# design.net
KiCad netlist of a schematic drawn in EasyEDA Pro
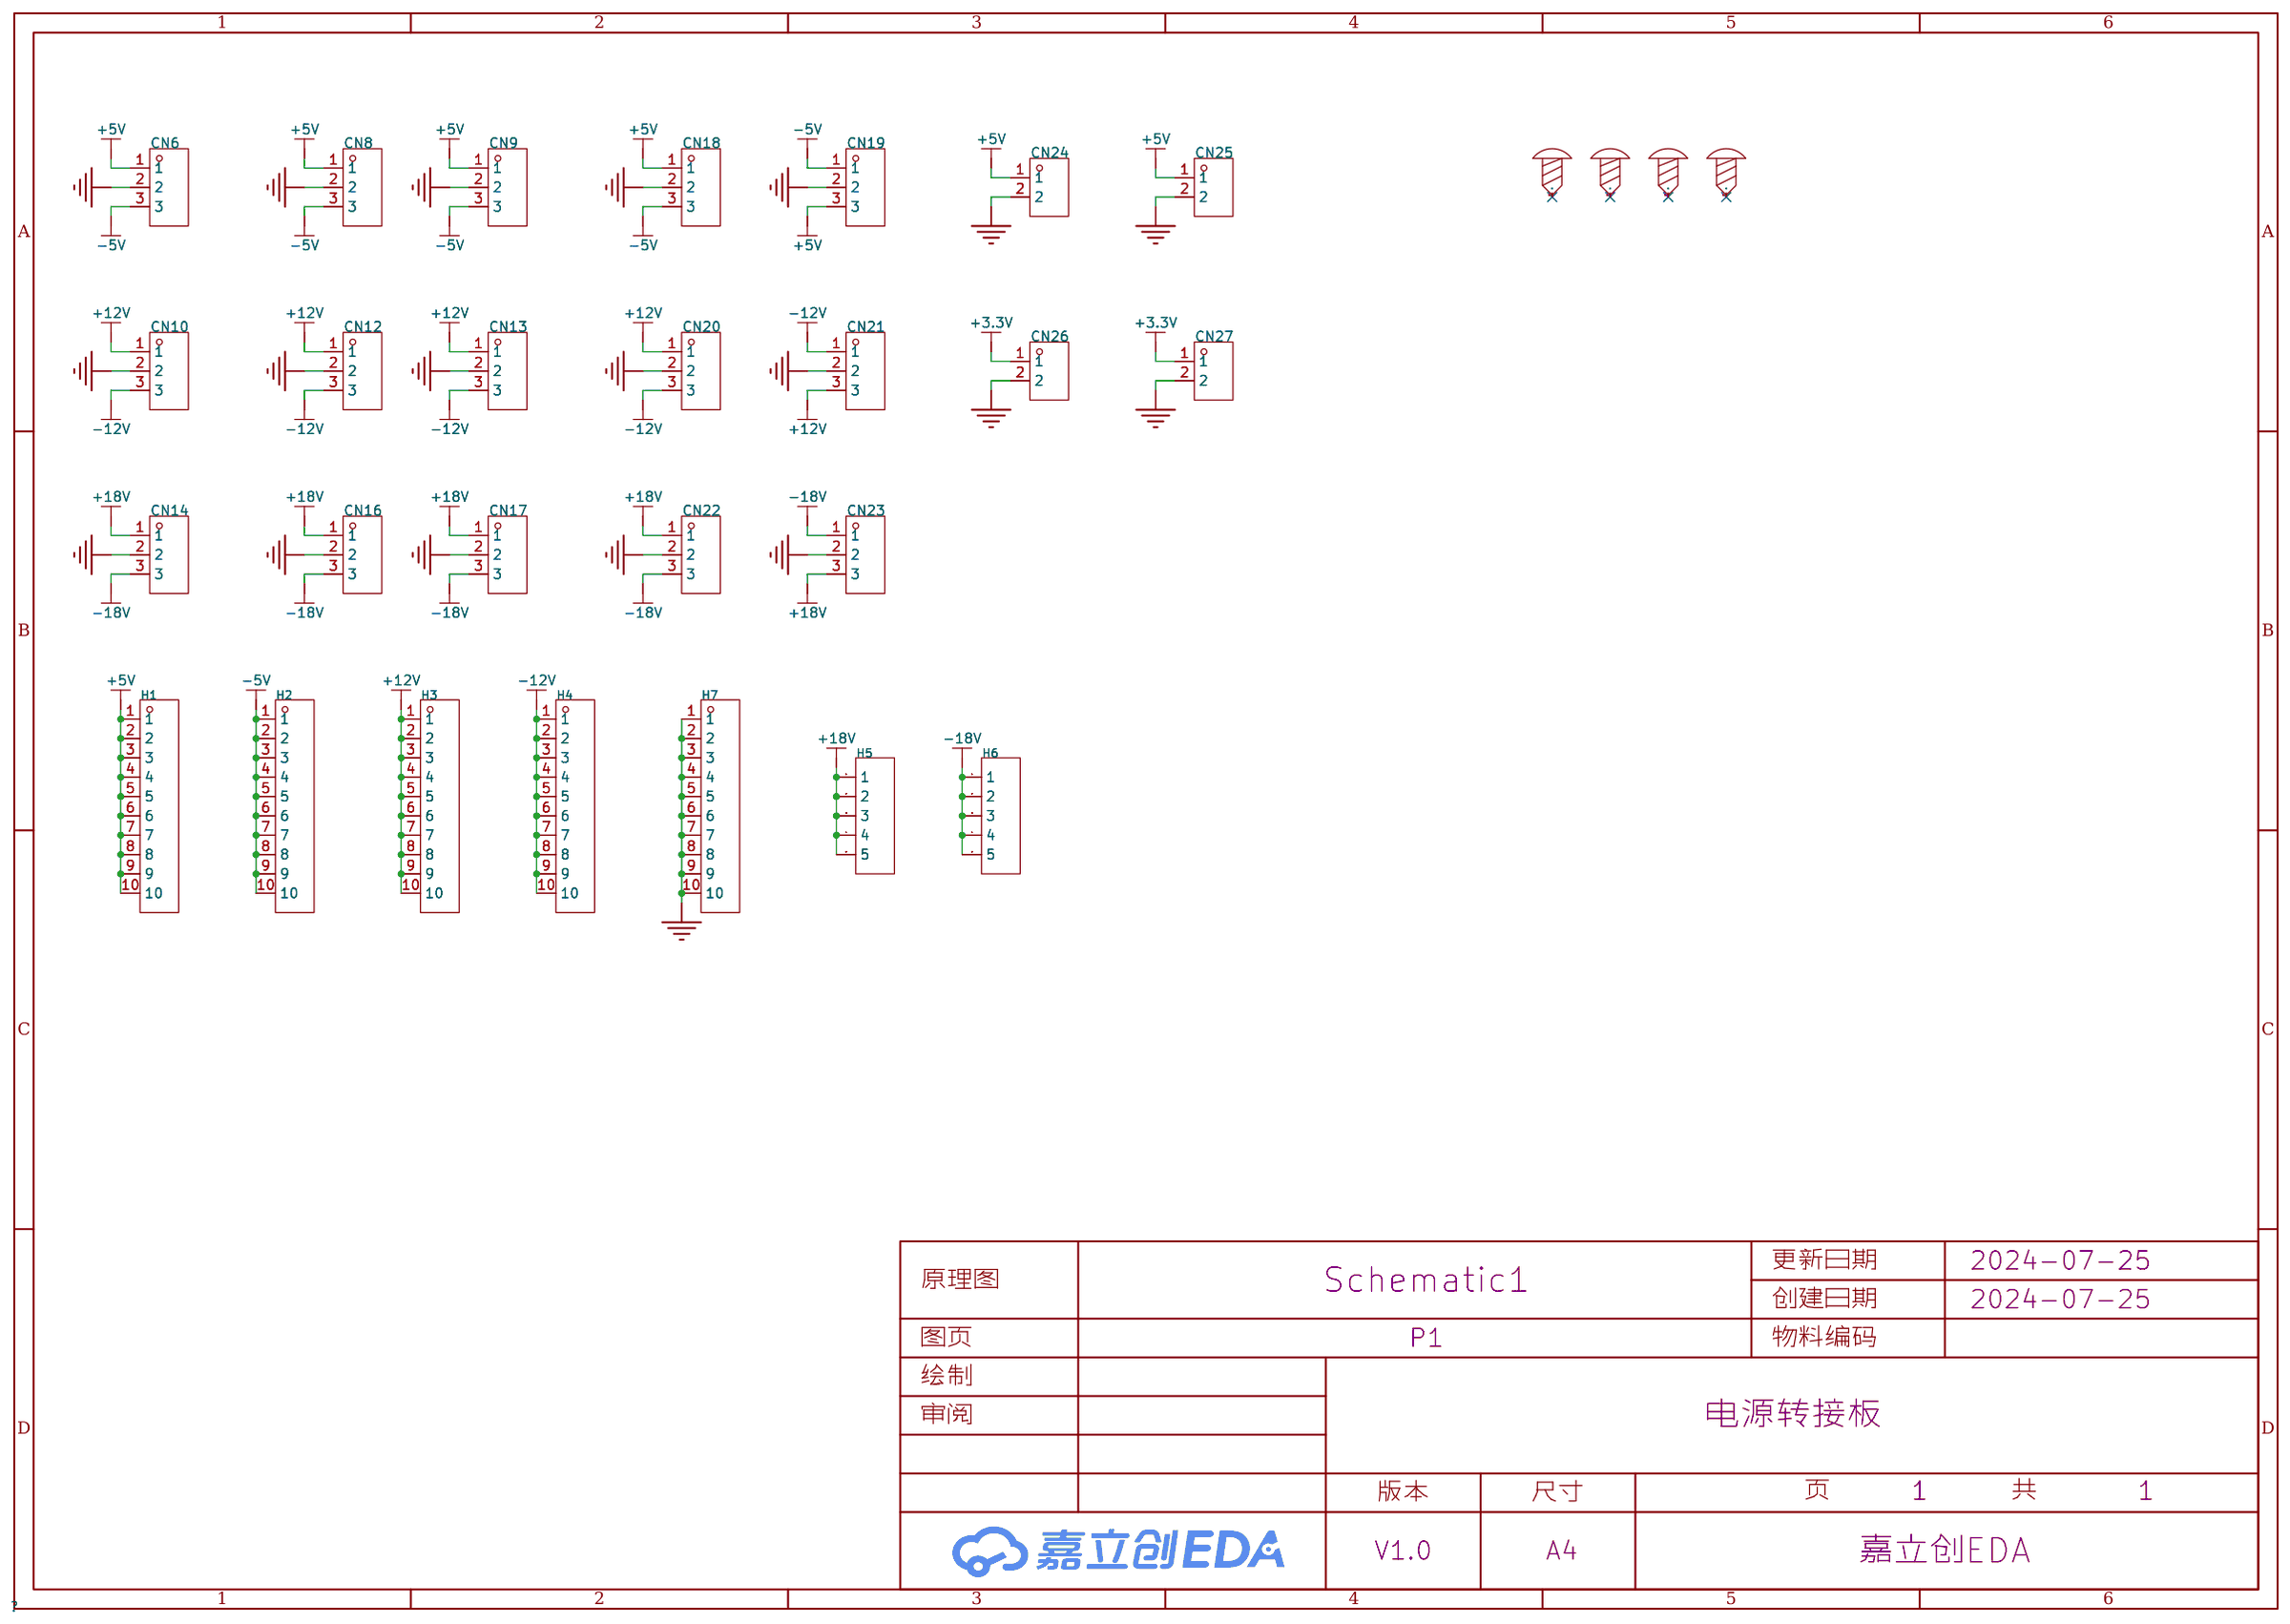
[diagram p0: schematic sheet]

(export (version "E")
  (design (tool "Eeschema 10.0.6"))
  (components
    (comp (ref "CN6")
      (value "DB2EVC-3.81-3P-GN")
      (footprint "easyedapro:CONN-TH_3P-P3.81_DB2EVC-3.81-3P")
      (fields (field (name "Manufacturer") "DORABO(地博电气)"))
      (libsource (lib "easyedapro") (part "DB2EVC-3.81-3P"))
    )
    (comp (ref "CN8")
      (value "DB2EVC-3.81-3P-GN")
      (footprint "easyedapro:CONN-TH_3P-P3.81_DB2EVC-3.81-3P")
      (fields (field (name "Manufacturer") "DORABO(地博电气)"))
      (libsource (lib "easyedapro") (part "DB2EVC-3.81-3P"))
    )
    (comp (ref "CN9")
      (value "DB2EVC-3.81-3P-GN")
      (footprint "easyedapro:CONN-TH_3P-P3.81_DB2EVC-3.81-3P")
      (fields (field (name "Manufacturer") "DORABO(地博电气)"))
      (libsource (lib "easyedapro") (part "DB2EVC-3.81-3P"))
    )
    (comp (ref "CN10")
      (value "DB2EVC-3.81-3P-GN")
      (footprint "easyedapro:CONN-TH_3P-P3.81_DB2EVC-3.81-3P")
      (fields (field (name "Manufacturer") "DORABO(地博电气)"))
      (libsource (lib "easyedapro") (part "DB2EVC-3.81-3P"))
    )
    (comp (ref "CN12")
      (value "DB2EVC-3.81-3P-GN")
      (footprint "easyedapro:CONN-TH_3P-P3.81_DB2EVC-3.81-3P")
      (fields (field (name "Manufacturer") "DORABO(地博电气)"))
      (libsource (lib "easyedapro") (part "DB2EVC-3.81-3P"))
    )
    (comp (ref "CN13")
      (value "DB2EVC-3.81-3P-GN")
      (footprint "easyedapro:CONN-TH_3P-P3.81_DB2EVC-3.81-3P")
      (fields (field (name "Manufacturer") "DORABO(地博电气)"))
      (libsource (lib "easyedapro") (part "DB2EVC-3.81-3P"))
    )
    (comp (ref "CN14")
      (value "DB2EVC-3.81-3P-GN")
      (footprint "easyedapro:CONN-TH_3P-P3.81_DB2EVC-3.81-3P")
      (fields (field (name "Manufacturer") "DORABO(地博电气)"))
      (libsource (lib "easyedapro") (part "DB2EVC-3.81-3P"))
    )
    (comp (ref "CN16")
      (value "DB2EVC-3.81-3P-GN")
      (footprint "easyedapro:CONN-TH_3P-P3.81_DB2EVC-3.81-3P")
      (fields (field (name "Manufacturer") "DORABO(地博电气)"))
      (libsource (lib "easyedapro") (part "DB2EVC-3.81-3P"))
    )
    (comp (ref "CN17")
      (value "DB2EVC-3.81-3P-GN")
      (footprint "easyedapro:CONN-TH_3P-P3.81_DB2EVC-3.81-3P")
      (fields (field (name "Manufacturer") "DORABO(地博电气)"))
      (libsource (lib "easyedapro") (part "DB2EVC-3.81-3P"))
    )
    (comp (ref "CN18")
      (value "MX301-5.0-03P-BU01-Cu-Y-A")
      (footprint "easyedapro:CONN-TH_3P-P5.0-MX301-5.0-03P-BU01-CU-Y-A")
      (fields (field (name "Manufacturer") "MAX(迈旭)"))
      (libsource (lib "easyedapro") (part "MX301-5.0-03P-BU01-CU-Y-A"))
    )
    (comp (ref "CN19")
      (value "MX301-5.0-03P-BU01-Cu-Y-A")
      (footprint "easyedapro:CONN-TH_3P-P5.0-MX301-5.0-03P-BU01-CU-Y-A")
      (fields (field (name "Manufacturer") "MAX(迈旭)"))
      (libsource (lib "easyedapro") (part "MX301-5.0-03P-BU01-CU-Y-A"))
    )
    (comp (ref "CN20")
      (value "MX301-5.0-03P-BU01-Cu-Y-A")
      (footprint "easyedapro:CONN-TH_3P-P5.0-MX301-5.0-03P-BU01-CU-Y-A")
      (fields (field (name "Manufacturer") "MAX(迈旭)"))
      (libsource (lib "easyedapro") (part "MX301-5.0-03P-BU01-CU-Y-A"))
    )
    (comp (ref "CN21")
      (value "MX301-5.0-03P-BU01-Cu-Y-A")
      (footprint "easyedapro:CONN-TH_3P-P5.0-MX301-5.0-03P-BU01-CU-Y-A")
      (fields (field (name "Manufacturer") "MAX(迈旭)"))
      (libsource (lib "easyedapro") (part "MX301-5.0-03P-BU01-CU-Y-A"))
    )
    (comp (ref "CN22")
      (value "MX301-5.0-03P-BU01-Cu-Y-A")
      (footprint "easyedapro:CONN-TH_3P-P5.0-MX301-5.0-03P-BU01-CU-Y-A")
      (fields (field (name "Manufacturer") "MAX(迈旭)"))
      (libsource (lib "easyedapro") (part "MX301-5.0-03P-BU01-CU-Y-A"))
    )
    (comp (ref "CN23")
      (value "MX301-5.0-03P-BU01-Cu-Y-A")
      (footprint "easyedapro:CONN-TH_3P-P5.0-MX301-5.0-03P-BU01-CU-Y-A")
      (fields (field (name "Manufacturer") "MAX(迈旭)"))
      (libsource (lib "easyedapro") (part "MX301-5.0-03P-BU01-CU-Y-A"))
    )
    (comp (ref "CN24")
      (value "ZX-XH2.54-2PZZ")
      (footprint "easyedapro:CONN-TH_2P-P2.50_HX25003-2A")
      (fields (field (name "Manufacturer") "Megastar(兆星)"))
      (libsource (lib "easyedapro") (part "ZX-XH2.54-2PZZ"))
    )
    (comp (ref "CN25")
      (value "ZX-XH2.54-2PZZ")
      (footprint "easyedapro:CONN-TH_2P-P2.50_HX25003-2A")
      (fields (field (name "Manufacturer") "Megastar(兆星)"))
      (libsource (lib "easyedapro") (part "ZX-XH2.54-2PZZ"))
    )
    (comp (ref "CN26")
      (value "ZX-XH2.54-2PZZ")
      (footprint "easyedapro:CONN-TH_2P-P2.50_HX25003-2A")
      (fields (field (name "Manufacturer") "Megastar(兆星)"))
      (libsource (lib "easyedapro") (part "ZX-XH2.54-2PZZ"))
    )
    (comp (ref "CN27")
      (value "ZX-XH2.54-2PZZ")
      (footprint "easyedapro:CONN-TH_2P-P2.50_HX25003-2A")
      (fields (field (name "Manufacturer") "Megastar(兆星)"))
      (libsource (lib "easyedapro") (part "ZX-XH2.54-2PZZ"))
    )
    (comp (ref "H1")
      (value "~")
      (footprint "easyedapro:HDR-TH_10P-P2.54-V-F")
      (libsource (lib "easyedapro") (part "X5511FV-10-C70D30-1000"))
    )
    (comp (ref "H2")
      (value "~")
      (footprint "easyedapro:HDR-TH_10P-P2.54-V-F")
      (libsource (lib "easyedapro") (part "X5511FV-10-C70D30-1000"))
    )
    (comp (ref "H3")
      (value "~")
      (footprint "easyedapro:HDR-TH_10P-P2.54-V-F")
      (libsource (lib "easyedapro") (part "X5511FV-10-C70D30-1000"))
    )
    (comp (ref "H4")
      (value "~")
      (footprint "easyedapro:HDR-TH_10P-P2.54-V-F")
      (libsource (lib "easyedapro") (part "X5511FV-10-C70D30-1000"))
    )
    (comp (ref "H5")
      (value "~")
      (footprint "easyedapro:HDR-TH_5P-P2.54-V-F")
      (libsource (lib "easyedapro") (part "Header-Female-2.54_1x5"))
    )
    (comp (ref "H6")
      (value "~")
      (footprint "easyedapro:HDR-TH_5P-P2.54-V-F")
      (libsource (lib "easyedapro") (part "Header-Female-2.54_1x5"))
    )
    (comp (ref "H7")
      (value "~")
      (footprint "easyedapro:HDR-TH_10P-P2.54-V-F")
      (libsource (lib "easyedapro") (part "X5511FV-10-C70D30-1000"))
    )
    (comp (ref "TP1") (value "~") (footprint "easyedapro:M3螺丝") (libsource (lib "easyedapro") (part "螺丝孔")))
    (comp (ref "TP2") (value "~") (footprint "easyedapro:M3螺丝") (libsource (lib "easyedapro") (part "螺丝孔")))
    (comp (ref "TP3") (value "~") (footprint "easyedapro:M3螺丝") (libsource (lib "easyedapro") (part "螺丝孔")))
    (comp (ref "TP4") (value "~") (footprint "easyedapro:M3螺丝") (libsource (lib "easyedapro") (part "螺丝孔")))
  )
  (nets
    (net (code "1") (name "+3.3V") (class "Default")
      (node (ref "CN26") (pin "1") (pinfunction "1_1") (pintype "unspecified"))
      (node (ref "CN27") (pin "1") (pinfunction "1_1") (pintype "unspecified"))
    )
    (net (code "2") (name "+5V") (class "Default")
      (node (ref "CN18") (pin "1") (pinfunction "1_1") (pintype "unspecified"))
      (node (ref "CN19") (pin "3") (pinfunction "3_3") (pintype "unspecified"))
      (node (ref "CN24") (pin "1") (pinfunction "1_1") (pintype "unspecified"))
      (node (ref "CN25") (pin "1") (pinfunction "1_1") (pintype "unspecified"))
      (node (ref "CN6") (pin "1") (pinfunction "1_1") (pintype "unspecified"))
      (node (ref "CN8") (pin "1") (pinfunction "1_1") (pintype "unspecified"))
      (node (ref "CN9") (pin "1") (pinfunction "1_1") (pintype "unspecified"))
      (node (ref "H1") (pin "1") (pinfunction "1_1") (pintype "input"))
      (node (ref "H1") (pin "10") (pinfunction "10_10") (pintype "input"))
      (node (ref "H1") (pin "2") (pinfunction "2_2") (pintype "input"))
      (node (ref "H1") (pin "3") (pinfunction "3_3") (pintype "input"))
      (node (ref "H1") (pin "4") (pinfunction "4_4") (pintype "input"))
      (node (ref "H1") (pin "5") (pinfunction "5_5") (pintype "input"))
      (node (ref "H1") (pin "6") (pinfunction "6_6") (pintype "input"))
      (node (ref "H1") (pin "7") (pinfunction "7_7") (pintype "input"))
      (node (ref "H1") (pin "8") (pinfunction "8_8") (pintype "input"))
      (node (ref "H1") (pin "9") (pinfunction "9_9") (pintype "input"))
    )
    (net (code "3") (name "+12V") (class "Default")
      (node (ref "CN10") (pin "1") (pinfunction "1_1") (pintype "unspecified"))
      (node (ref "CN12") (pin "1") (pinfunction "1_1") (pintype "unspecified"))
      (node (ref "CN13") (pin "1") (pinfunction "1_1") (pintype "unspecified"))
      (node (ref "CN20") (pin "1") (pinfunction "1_1") (pintype "unspecified"))
      (node (ref "CN21") (pin "3") (pinfunction "3_3") (pintype "unspecified"))
      (node (ref "H3") (pin "1") (pinfunction "1_1") (pintype "input"))
      (node (ref "H3") (pin "10") (pinfunction "10_10") (pintype "input"))
      (node (ref "H3") (pin "2") (pinfunction "2_2") (pintype "input"))
      (node (ref "H3") (pin "3") (pinfunction "3_3") (pintype "input"))
      (node (ref "H3") (pin "4") (pinfunction "4_4") (pintype "input"))
      (node (ref "H3") (pin "5") (pinfunction "5_5") (pintype "input"))
      (node (ref "H3") (pin "6") (pinfunction "6_6") (pintype "input"))
      (node (ref "H3") (pin "7") (pinfunction "7_7") (pintype "input"))
      (node (ref "H3") (pin "8") (pinfunction "8_8") (pintype "input"))
      (node (ref "H3") (pin "9") (pinfunction "9_9") (pintype "input"))
    )
    (net (code "4") (name "+18V") (class "Default")
      (node (ref "CN14") (pin "1") (pinfunction "1_1") (pintype "unspecified"))
      (node (ref "CN16") (pin "1") (pinfunction "1_1") (pintype "unspecified"))
      (node (ref "CN17") (pin "1") (pinfunction "1_1") (pintype "unspecified"))
      (node (ref "CN22") (pin "1") (pinfunction "1_1") (pintype "unspecified"))
      (node (ref "CN23") (pin "3") (pinfunction "3_3") (pintype "unspecified"))
      (node (ref "H5") (pin "1") (pinfunction "1_1") (pintype "input"))
      (node (ref "H5") (pin "2") (pinfunction "2_2") (pintype "input"))
      (node (ref "H5") (pin "3") (pinfunction "3_3") (pintype "input"))
      (node (ref "H5") (pin "4") (pinfunction "4_4") (pintype "input"))
      (node (ref "H5") (pin "5") (pinfunction "5_5") (pintype "input"))
    )
    (net (code "5") (name "-5V") (class "Default")
      (node (ref "CN18") (pin "3") (pinfunction "3_3") (pintype "unspecified"))
      (node (ref "CN19") (pin "1") (pinfunction "1_1") (pintype "unspecified"))
      (node (ref "CN6") (pin "3") (pinfunction "3_3") (pintype "unspecified"))
      (node (ref "CN8") (pin "3") (pinfunction "3_3") (pintype "unspecified"))
      (node (ref "CN9") (pin "3") (pinfunction "3_3") (pintype "unspecified"))
      (node (ref "H2") (pin "1") (pinfunction "1_1") (pintype "input"))
      (node (ref "H2") (pin "10") (pinfunction "10_10") (pintype "input"))
      (node (ref "H2") (pin "2") (pinfunction "2_2") (pintype "input"))
      (node (ref "H2") (pin "3") (pinfunction "3_3") (pintype "input"))
      (node (ref "H2") (pin "4") (pinfunction "4_4") (pintype "input"))
      (node (ref "H2") (pin "5") (pinfunction "5_5") (pintype "input"))
      (node (ref "H2") (pin "6") (pinfunction "6_6") (pintype "input"))
      (node (ref "H2") (pin "7") (pinfunction "7_7") (pintype "input"))
      (node (ref "H2") (pin "8") (pinfunction "8_8") (pintype "input"))
      (node (ref "H2") (pin "9") (pinfunction "9_9") (pintype "input"))
    )
    (net (code "6") (name "-12V") (class "Default")
      (node (ref "CN10") (pin "3") (pinfunction "3_3") (pintype "unspecified"))
      (node (ref "CN12") (pin "3") (pinfunction "3_3") (pintype "unspecified"))
      (node (ref "CN13") (pin "3") (pinfunction "3_3") (pintype "unspecified"))
      (node (ref "CN20") (pin "3") (pinfunction "3_3") (pintype "unspecified"))
      (node (ref "CN21") (pin "1") (pinfunction "1_1") (pintype "unspecified"))
      (node (ref "H4") (pin "1") (pinfunction "1_1") (pintype "input"))
      (node (ref "H4") (pin "10") (pinfunction "10_10") (pintype "input"))
      (node (ref "H4") (pin "2") (pinfunction "2_2") (pintype "input"))
      (node (ref "H4") (pin "3") (pinfunction "3_3") (pintype "input"))
      (node (ref "H4") (pin "4") (pinfunction "4_4") (pintype "input"))
      (node (ref "H4") (pin "5") (pinfunction "5_5") (pintype "input"))
      (node (ref "H4") (pin "6") (pinfunction "6_6") (pintype "input"))
      (node (ref "H4") (pin "7") (pinfunction "7_7") (pintype "input"))
      (node (ref "H4") (pin "8") (pinfunction "8_8") (pintype "input"))
      (node (ref "H4") (pin "9") (pinfunction "9_9") (pintype "input"))
    )
    (net (code "7") (name "-18V") (class "Default")
      (node (ref "CN14") (pin "3") (pinfunction "3_3") (pintype "unspecified"))
      (node (ref "CN16") (pin "3") (pinfunction "3_3") (pintype "unspecified"))
      (node (ref "CN17") (pin "3") (pinfunction "3_3") (pintype "unspecified"))
      (node (ref "CN22") (pin "3") (pinfunction "3_3") (pintype "unspecified"))
      (node (ref "CN23") (pin "1") (pinfunction "1_1") (pintype "unspecified"))
      (node (ref "H6") (pin "1") (pinfunction "1_1") (pintype "input"))
      (node (ref "H6") (pin "2") (pinfunction "2_2") (pintype "input"))
      (node (ref "H6") (pin "3") (pinfunction "3_3") (pintype "input"))
      (node (ref "H6") (pin "4") (pinfunction "4_4") (pintype "input"))
      (node (ref "H6") (pin "5") (pinfunction "5_5") (pintype "input"))
    )
    (net (code "8") (name "GND") (class "Default")
      (node (ref "CN10") (pin "2") (pinfunction "2_2") (pintype "unspecified"))
      (node (ref "CN12") (pin "2") (pinfunction "2_2") (pintype "unspecified"))
      (node (ref "CN13") (pin "2") (pinfunction "2_2") (pintype "unspecified"))
      (node (ref "CN14") (pin "2") (pinfunction "2_2") (pintype "unspecified"))
      (node (ref "CN16") (pin "2") (pinfunction "2_2") (pintype "unspecified"))
      (node (ref "CN17") (pin "2") (pinfunction "2_2") (pintype "unspecified"))
      (node (ref "CN18") (pin "2") (pinfunction "2_2") (pintype "unspecified"))
      (node (ref "CN19") (pin "2") (pinfunction "2_2") (pintype "unspecified"))
      (node (ref "CN20") (pin "2") (pinfunction "2_2") (pintype "unspecified"))
      (node (ref "CN21") (pin "2") (pinfunction "2_2") (pintype "unspecified"))
      (node (ref "CN22") (pin "2") (pinfunction "2_2") (pintype "unspecified"))
      (node (ref "CN23") (pin "2") (pinfunction "2_2") (pintype "unspecified"))
      (node (ref "CN24") (pin "2") (pinfunction "2_2") (pintype "unspecified"))
      (node (ref "CN25") (pin "2") (pinfunction "2_2") (pintype "unspecified"))
      (node (ref "CN26") (pin "2") (pinfunction "2_2") (pintype "unspecified"))
      (node (ref "CN27") (pin "2") (pinfunction "2_2") (pintype "unspecified"))
      (node (ref "CN6") (pin "2") (pinfunction "2_2") (pintype "unspecified"))
      (node (ref "CN8") (pin "2") (pinfunction "2_2") (pintype "unspecified"))
      (node (ref "CN9") (pin "2") (pinfunction "2_2") (pintype "unspecified"))
      (node (ref "H7") (pin "1") (pinfunction "1_1") (pintype "input"))
      (node (ref "H7") (pin "10") (pinfunction "10_10") (pintype "input"))
      (node (ref "H7") (pin "2") (pinfunction "2_2") (pintype "input"))
      (node (ref "H7") (pin "3") (pinfunction "3_3") (pintype "input"))
      (node (ref "H7") (pin "4") (pinfunction "4_4") (pintype "input"))
      (node (ref "H7") (pin "5") (pinfunction "5_5") (pintype "input"))
      (node (ref "H7") (pin "6") (pinfunction "6_6") (pintype "input"))
      (node (ref "H7") (pin "7") (pinfunction "7_7") (pintype "input"))
      (node (ref "H7") (pin "8") (pinfunction "8_8") (pintype "input"))
      (node (ref "H7") (pin "9") (pinfunction "9_9") (pintype "input"))
    )
    (net (code "9") (name "unconnected-(TP1-Pad1)") (class "Default")
      (node (ref "TP1") (pin "1") (pinfunction "1_1") (pintype "input+no_connect"))
    )
    (net (code "10") (name "unconnected-(TP2-Pad1)") (class "Default")
      (node (ref "TP2") (pin "1") (pinfunction "1_1") (pintype "input+no_connect"))
    )
    (net (code "11") (name "unconnected-(TP3-Pad1)") (class "Default")
      (node (ref "TP3") (pin "1") (pinfunction "1_1") (pintype "input+no_connect"))
    )
    (net (code "12") (name "unconnected-(TP4-Pad1)") (class "Default")
      (node (ref "TP4") (pin "1") (pinfunction "1_1") (pintype "input+no_connect"))
    )
  )
)
